# Acoustics_Hydrophone_Process.net
KiCad netlist of a schematic drawn in Altium Designer
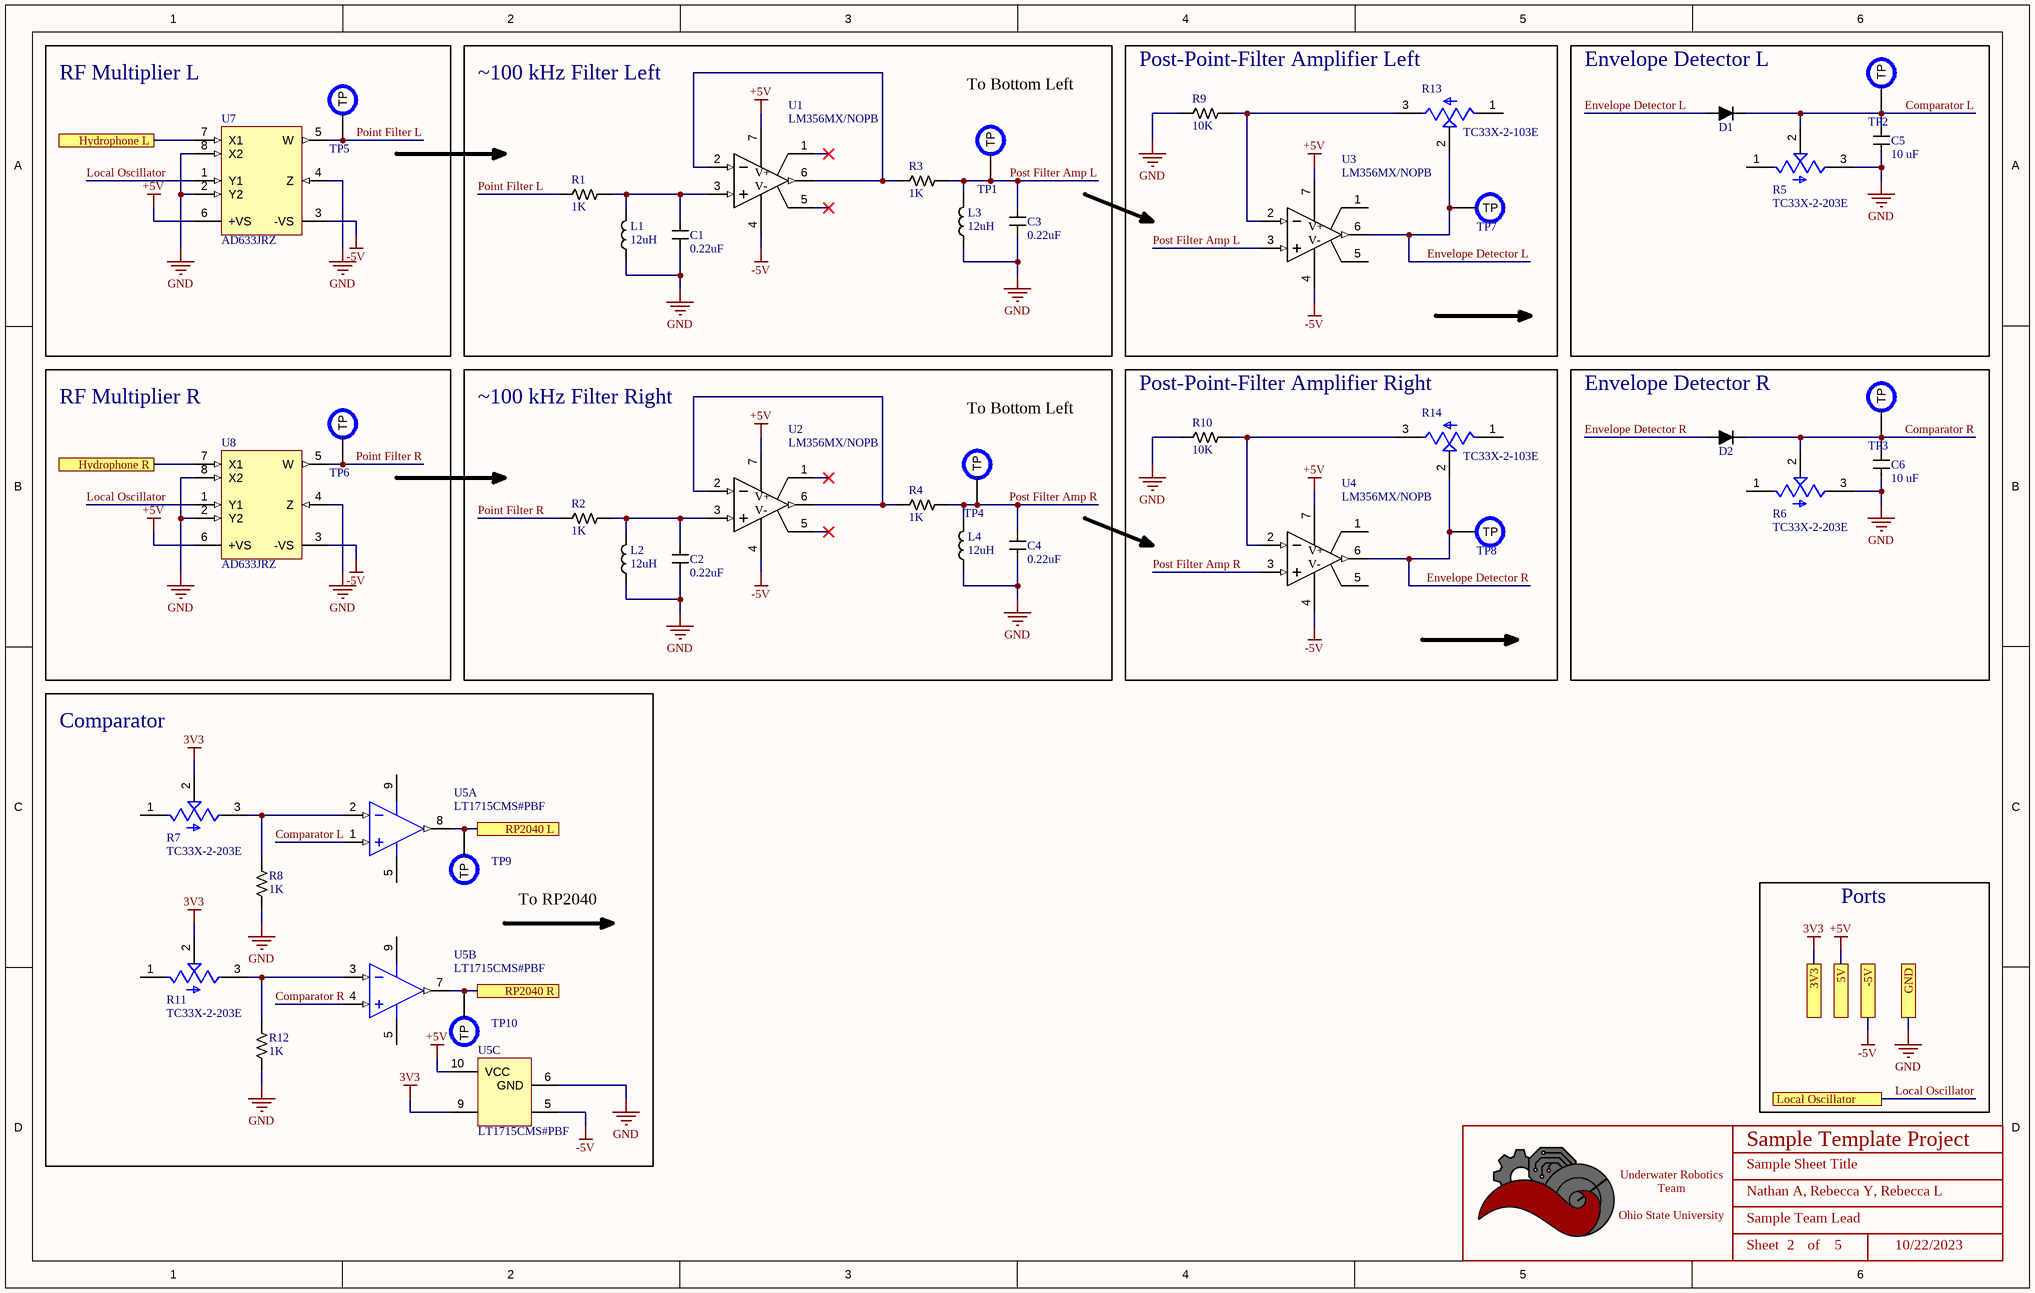
[diagram p0: [Acoustics] Hydrophone Process.SchDoc]

(export (version "E")
  (design (tool "Eeschema 10.0.6"))
  (components
    (comp (ref "C1")
      (value "0.22uF")
      (footprint "CAPACITOR_0603")
      (description "CAP CER 0.22uF 16V X7R 0603")
      (fields
        (field (name "TOLERANCE") "+/- 5%")
        (field (name "VOLTAGE") "16V")
        (field (name "MADE BY") "Nathan Ayer")
      )
      (libsource (lib "Capacitors") (part "CAPACITOR_0.000027uF_0603"))
    )
    (comp (ref "C2")
      (value "0.22uF")
      (footprint "CAPACITOR_0603")
      (description "CAP CER 0.22uF 16V X7R 0603")
      (fields
        (field (name "TOLERANCE") "+/- 5%")
        (field (name "VOLTAGE") "16V")
        (field (name "MADE BY") "Nathan Ayer")
      )
      (libsource (lib "Capacitors") (part "CAPACITOR_0.000027uF_0603"))
    )
    (comp (ref "C3")
      (value "0.22uF")
      (footprint "CAPACITOR_0603")
      (description "CAP CER 0.22uF 16V X7R 0603")
      (fields
        (field (name "TOLERANCE") "+/- 5%")
        (field (name "VOLTAGE") "16V")
        (field (name "MADE BY") "Nathan Ayer")
      )
      (libsource (lib "Capacitors") (part "CAPACITOR_0.000027uF_0603"))
    )
    (comp (ref "C4")
      (value "0.22uF")
      (footprint "CAPACITOR_0603")
      (description "CAP CER 0.22uF 16V X7R 0603")
      (fields
        (field (name "TOLERANCE") "+/- 5%")
        (field (name "VOLTAGE") "16V")
        (field (name "MADE BY") "Nathan Ayer")
      )
      (libsource (lib "Capacitors") (part "CAPACITOR_0.000027uF_0603"))
    )
    (comp (ref "C5")
      (value "10uF Ceramic 6.3V")
      (footprint "CAPACITOR_0603")
      (description "Cap 10uF 6.3V +/-20%\r\nCeramic 0603")
      (fields
        (field (name "TOLERANCE") "+/- 20%")
        (field (name "VOLTAGE") "6.3V")
        (field (name "VALUE (UF)") "10 uF")
        (field (name "MADE BY") "Flip B")
      )
      (libsource (lib "Capacitors") (part "CAPACITOR_10uF_0603"))
    )
    (comp (ref "C6")
      (value "10uF Ceramic 6.3V")
      (footprint "CAPACITOR_0603")
      (description "Cap 10uF 6.3V +/-20%\r\nCeramic 0603")
      (fields
        (field (name "TOLERANCE") "+/- 20%")
        (field (name "VOLTAGE") "6.3V")
        (field (name "VALUE (UF)") "10 uF")
        (field (name "MADE BY") "Flip B")
      )
      (libsource (lib "Capacitors") (part "CAPACITOR_10uF_0603"))
    )
    (comp (ref "D1")
      (value "BAR9002ELE6327XTMA1")
      (footprint "DIODE_0402")
      (description "RF Diode PIN - Single 80V 100 mA 250 mW PG-TSLP-2-19")
      (libsource (lib "Diodes") (part "RF Diode 80V 100mA"))
    )
    (comp (ref "D2")
      (value "BAR9002ELE6327XTMA1")
      (footprint "DIODE_0402")
      (description "RF Diode PIN - Single 80V 100 mA 250 mW PG-TSLP-2-19")
      (libsource (lib "Diodes") (part "RF Diode 80V 100mA"))
    )
    (comp (ref "L1")
      (value "12uH")
      (footprint "INDUCTOR_0603")
      (description "12 µH Shielded Multilayer Inductor 10 mA 1.8Ohm Max 0603 (1608 Metric)")
      (fields
        (field (name "TOLERANCE") "+/- 5%")
        (field (name "Comment") "FIXED IND 12UH 10MA 1.8 OHM SMD")
        (field (name "MADE BY") "Nathan Ayer")
      )
      (libsource (lib "Inductors") (part "INDUCTOR_12uH_0603"))
    )
    (comp (ref "L2")
      (value "12uH")
      (footprint "INDUCTOR_0603")
      (description "12 µH Shielded Multilayer Inductor 10 mA 1.8Ohm Max 0603 (1608 Metric)")
      (fields
        (field (name "TOLERANCE") "+/- 5%")
        (field (name "Comment") "FIXED IND 12UH 10MA 1.8 OHM SMD")
        (field (name "MADE BY") "Nathan Ayer")
      )
      (libsource (lib "Inductors") (part "INDUCTOR_12uH_0603"))
    )
    (comp (ref "L3")
      (value "12uH")
      (footprint "INDUCTOR_0603")
      (description "12 µH Shielded Multilayer Inductor 10 mA 1.8Ohm Max 0603 (1608 Metric)")
      (fields
        (field (name "TOLERANCE") "+/- 5%")
        (field (name "Comment") "FIXED IND 12UH 10MA 1.8 OHM SMD")
        (field (name "MADE BY") "Nathan Ayer")
      )
      (libsource (lib "Inductors") (part "INDUCTOR_12uH_0603"))
    )
    (comp (ref "L4")
      (value "12uH")
      (footprint "INDUCTOR_0603")
      (description "12 µH Shielded Multilayer Inductor 10 mA 1.8Ohm Max 0603 (1608 Metric)")
      (fields
        (field (name "TOLERANCE") "+/- 5%")
        (field (name "Comment") "FIXED IND 12UH 10MA 1.8 OHM SMD")
        (field (name "MADE BY") "Nathan Ayer")
      )
      (libsource (lib "Inductors") (part "INDUCTOR_12uH_0603"))
    )
    (comp (ref "R1")
      (value "1.45k Ohm 0.1% 1/10W")
      (footprint "RESISTOR_0603")
      (description "RES 1.45K OHM 0.1% 1/10W 0603")
      (fields
        (field (name "TOLERANCE") "+/- 0.1%")
        (field (name "VALUE  (OHMS)") "1K")
        (field (name "MADE BY") "Nathan Ayer")
      )
      (libsource (lib "Resistors") (part "RESISTOR_1K_0603"))
    )
    (comp (ref "R2")
      (value "1.45k Ohm 0.1% 1/10W")
      (footprint "RESISTOR_0603")
      (description "RES 1.45K OHM 0.1% 1/10W 0603")
      (fields
        (field (name "TOLERANCE") "+/- 0.1%")
        (field (name "VALUE  (OHMS)") "1K")
        (field (name "MADE BY") "Nathan Ayer")
      )
      (libsource (lib "Resistors") (part "RESISTOR_1K_0603"))
    )
    (comp (ref "R3")
      (value "1.45k Ohm 0.1% 1/10W")
      (footprint "RESISTOR_0603")
      (description "RES 1.45K OHM 0.1% 1/10W 0603")
      (fields
        (field (name "TOLERANCE") "+/- 0.1%")
        (field (name "VALUE  (OHMS)") "1K")
        (field (name "MADE BY") "Nathan Ayer")
      )
      (libsource (lib "Resistors") (part "RESISTOR_1K_0603"))
    )
    (comp (ref "R4")
      (value "1.45k Ohm 0.1% 1/10W")
      (footprint "RESISTOR_0603")
      (description "RES 1.45K OHM 0.1% 1/10W 0603")
      (fields
        (field (name "TOLERANCE") "+/- 0.1%")
        (field (name "VALUE  (OHMS)") "1K")
        (field (name "MADE BY") "Nathan Ayer")
      )
      (libsource (lib "Resistors") (part "RESISTOR_1K_0603"))
    )
    (comp (ref "R5")
      (value "TC33X-2-203E")
      (footprint "TRIM_TC33X-2-203E")
      (description "20 kOhms 0.1W, 1/10W J Lead Surface Mount Trimmer Potentiometer Cermet 1 Turn Top Adjustment")
      (fields (field (name "MF") "Bourns") (field (name "DIGI-KEY_PART_NUMBER") "TC33X-2-203ECT-ND"))
      (libsource (lib "Resistors") (part "TC33X-2-203E"))
    )
    (comp (ref "R6")
      (value "TC33X-2-203E")
      (footprint "TRIM_TC33X-2-203E")
      (description "20 kOhms 0.1W, 1/10W J Lead Surface Mount Trimmer Potentiometer Cermet 1 Turn Top Adjustment")
      (fields (field (name "MF") "Bourns") (field (name "DIGI-KEY_PART_NUMBER") "TC33X-2-203ECT-ND"))
      (libsource (lib "Resistors") (part "TC33X-2-203E"))
    )
    (comp (ref "R7")
      (value "TC33X-2-203E")
      (footprint "TRIM_TC33X-2-203E")
      (description "20 kOhms 0.1W, 1/10W J Lead Surface Mount Trimmer Potentiometer Cermet 1 Turn Top Adjustment")
      (fields (field (name "MF") "Bourns") (field (name "DIGI-KEY_PART_NUMBER") "TC33X-2-203ECT-ND"))
      (libsource (lib "Resistors") (part "TC33X-2-203E"))
    )
    (comp (ref "R8")
      (value "1k Ohm 1% 1/16W")
      (footprint "RESISTOR_0402")
      (description "RES 1k OHM 1% 1/16W 0402")
      (fields
        (field (name "TOLERANCE") "+/- 1%")
        (field (name "VALUE  (OHMS)") "1K")
        (field (name "MADE BY") "Robert Pafford")
      )
      (libsource (lib "Resistors") (part "RESISTOR_1K_0402"))
    )
    (comp (ref "R9")
      (value "10k Ohm 0.5% 1/10W")
      (footprint "RESISTOR_0603")
      (description "RES 10k OHM 0.5% 1/10W 0603")
      (fields
        (field (name "TOLERANCE") "+/- 0.5%")
        (field (name "VALUE  (OHMS)") "10K")
        (field (name "MADE BY") "Robert Pafford")
      )
      (libsource (lib "Resistors") (part "RESISTOR_10K_0.5%_0603"))
    )
    (comp (ref "R10")
      (value "10k Ohm 0.5% 1/10W")
      (footprint "RESISTOR_0603")
      (description "RES 10k OHM 0.5% 1/10W 0603")
      (fields
        (field (name "TOLERANCE") "+/- 0.5%")
        (field (name "VALUE  (OHMS)") "10K")
        (field (name "MADE BY") "Robert Pafford")
      )
      (libsource (lib "Resistors") (part "RESISTOR_10K_0.5%_0603"))
    )
    (comp (ref "R11")
      (value "TC33X-2-203E")
      (footprint "TRIM_TC33X-2-203E")
      (description "20 kOhms 0.1W, 1/10W J Lead Surface Mount Trimmer Potentiometer Cermet 1 Turn Top Adjustment")
      (fields (field (name "MF") "Bourns") (field (name "DIGI-KEY_PART_NUMBER") "TC33X-2-203ECT-ND"))
      (libsource (lib "Resistors") (part "TC33X-2-203E"))
    )
    (comp (ref "R12")
      (value "1k Ohm 1% 1/16W")
      (footprint "RESISTOR_0402")
      (description "RES 1k OHM 1% 1/16W 0402")
      (fields
        (field (name "TOLERANCE") "+/- 1%")
        (field (name "VALUE  (OHMS)") "1K")
        (field (name "MADE BY") "Robert Pafford")
      )
      (libsource (lib "Resistors") (part "RESISTOR_1K_0402"))
    )
    (comp (ref "R13")
      (value "TC33X-2-103E")
      (footprint "TRIM_TC33X-2-203E")
      (description "20 kOhms 0.1W, 1/10W J Lead Surface Mount Trimmer Potentiometer Cermet 1 Turn Top Adjustment")
      (fields (field (name "MF") "Bourns") (field (name "DIGI-KEY_PART_NUMBER") "TC33X-2-203ECT-ND"))
      (libsource (lib "Resistors") (part "TC33X-2-203E"))
    )
    (comp (ref "R14")
      (value "TC33X-2-103E")
      (footprint "TRIM_TC33X-2-203E")
      (description "20 kOhms 0.1W, 1/10W J Lead Surface Mount Trimmer Potentiometer Cermet 1 Turn Top Adjustment")
      (fields (field (name "MF") "Bourns") (field (name "DIGI-KEY_PART_NUMBER") "TC33X-2-203ECT-ND"))
      (libsource (lib "Resistors") (part "TC33X-2-203E"))
    )
    (comp (ref "TP1")
      (value "PCB Test Point")
      (footprint "TESTPOINT_1.2MM")
      (fields (field (name "MADE BY") "Robert Pafford"))
      (libsource (lib "Connectors") (part "TESTPOINT"))
    )
    (comp (ref "TP2")
      (value "PCB Test Point")
      (footprint "TESTPOINT_1.2MM")
      (fields (field (name "MADE BY") "Robert Pafford"))
      (libsource (lib "Connectors") (part "TESTPOINT"))
    )
    (comp (ref "TP3")
      (value "PCB Test Point")
      (footprint "TESTPOINT_1.2MM")
      (fields (field (name "MADE BY") "Robert Pafford"))
      (libsource (lib "Connectors") (part "TESTPOINT"))
    )
    (comp (ref "TP4")
      (value "PCB Test Point")
      (footprint "TESTPOINT_1.2MM")
      (fields (field (name "MADE BY") "Robert Pafford"))
      (libsource (lib "Connectors") (part "TESTPOINT"))
    )
    (comp (ref "TP5")
      (value "PCB Test Point")
      (footprint "TESTPOINT_1.2MM")
      (fields (field (name "MADE BY") "Robert Pafford"))
      (libsource (lib "Connectors") (part "TESTPOINT"))
    )
    (comp (ref "TP6")
      (value "PCB Test Point")
      (footprint "TESTPOINT_1.2MM")
      (fields (field (name "MADE BY") "Robert Pafford"))
      (libsource (lib "Connectors") (part "TESTPOINT"))
    )
    (comp (ref "TP7")
      (value "PCB Test Point")
      (footprint "TESTPOINT_1.2MM")
      (fields (field (name "MADE BY") "Robert Pafford"))
      (libsource (lib "Connectors") (part "TESTPOINT"))
    )
    (comp (ref "TP8")
      (value "PCB Test Point")
      (footprint "TESTPOINT_1.2MM")
      (fields (field (name "MADE BY") "Robert Pafford"))
      (libsource (lib "Connectors") (part "TESTPOINT"))
    )
    (comp (ref "TP9")
      (value "PCB Test Point")
      (footprint "TESTPOINT_1.2MM")
      (fields (field (name "MADE BY") "Robert Pafford"))
      (libsource (lib "Connectors") (part "TESTPOINT"))
    )
    (comp (ref "TP10")
      (value "PCB Test Point")
      (footprint "TESTPOINT_1.2MM")
      (fields (field (name "MADE BY") "Robert Pafford"))
      (libsource (lib "Connectors") (part "TESTPOINT"))
    )
    (comp (ref "U1")
      (value "LM356MX/NOPB")
      (footprint "SOIC-8")
      (description "IC OPAMP JFET 1 CIRCUIT 8SOIC")
      (fields
        (field (name "PARTNUMBER") "LM8261M5X/NOPB")
        (field (name "MANUFACTURER") "Texas Instruments")
        (field (name "CREATED BY") "Dylan T")
      )
      (libsource (lib "Integrated Circuits") (part "LM356MX/NOPB"))
    )
    (comp (ref "U2")
      (value "LM356MX/NOPB")
      (footprint "SOIC-8")
      (description "IC OPAMP JFET 1 CIRCUIT 8SOIC")
      (fields
        (field (name "PARTNUMBER") "LM8261M5X/NOPB")
        (field (name "MANUFACTURER") "Texas Instruments")
        (field (name "CREATED BY") "Dylan T")
      )
      (libsource (lib "Integrated Circuits") (part "LM356MX/NOPB"))
    )
    (comp (ref "U3")
      (value "LM356MX/NOPB")
      (footprint "SOIC-8")
      (description "IC OPAMP JFET 1 CIRCUIT 8SOIC")
      (fields
        (field (name "PARTNUMBER") "LM8261M5X/NOPB")
        (field (name "MANUFACTURER") "Texas Instruments")
        (field (name "CREATED BY") "Dylan T")
      )
      (libsource (lib "Integrated Circuits") (part "LM356MX/NOPB"))
    )
    (comp (ref "U4")
      (value "LM356MX/NOPB")
      (footprint "SOIC-8")
      (description "IC OPAMP JFET 1 CIRCUIT 8SOIC")
      (fields
        (field (name "PARTNUMBER") "LM8261M5X/NOPB")
        (field (name "MANUFACTURER") "Texas Instruments")
        (field (name "CREATED BY") "Dylan T")
      )
      (libsource (lib "Integrated Circuits") (part "LM356MX/NOPB"))
    )
    (comp (ref "U5")
      (value "LT1715CMS#PBF")
      (footprint "LT-MS10_N")
      (fields (field (name "GENERIC PART NUMBER") "LT1715") (field (name "MANUFACTURER") "Linear Technology"))
      (libsource (lib "") (part "LT-LT1715-MSOP10_1"))
    )
    (comp (ref "U7")
      (value "AD633JRZ")
      (footprint "ADI-R-8_M")
      (description "Low Cost Analog Multiplier, 20 V/us, 6 mA, 0 to 70 degC, 8-Pin SOIC (R), RoHS, Tube")
      (fields (field (name "PARTNUMBER") "AD633"))
      (libsource (lib "Altium Content Vault") (part "ADI-AD633-R-8"))
    )
    (comp (ref "U8")
      (value "AD633JRZ")
      (footprint "ADI-R-8_M")
      (description "Low Cost Analog Multiplier, 20 V/us, 6 mA, 0 to 70 degC, 8-Pin SOIC (R), RoHS, Tube")
      (fields (field (name "PARTNUMBER") "AD633"))
      (libsource (lib "Altium Content Vault") (part "ADI-AD633-R-8"))
    )
  )
  (nets
    (net (code "1") (name "+5V") (class "Default")
      (node (ref "U1") (pin "7") (pinfunction "V+_7") (pintype "power_in"))
      (node (ref "U2") (pin "7") (pinfunction "V+_7") (pintype "power_in"))
      (node (ref "U3") (pin "7") (pinfunction "V+_7") (pintype "power_in"))
      (node (ref "U4") (pin "7") (pinfunction "V+_7") (pintype "power_in"))
      (node (ref "U5") (pin "10") (pinfunction "VCC_10") (pintype "power_in"))
      (node (ref "U7") (pin "6") (pinfunction "+VS_6") (pintype "power_in"))
      (node (ref "U8") (pin "6") (pinfunction "+VS_6") (pintype "power_in"))
    )
    (net (code "2") (name "-5V") (class "Default")
      (node (ref "U1") (pin "4") (pinfunction "V-_4") (pintype "power_in"))
      (node (ref "U2") (pin "4") (pinfunction "V-_4") (pintype "power_in"))
      (node (ref "U3") (pin "4") (pinfunction "V-_4") (pintype "power_in"))
      (node (ref "U4") (pin "4") (pinfunction "V-_4") (pintype "power_in"))
      (node (ref "U5") (pin "5") (pinfunction "VEE_5") (pintype "power_in"))
      (node (ref "U7") (pin "3") (pinfunction "-VS_3") (pintype "power_in"))
      (node (ref "U8") (pin "3") (pinfunction "-VS_3") (pintype "power_in"))
    )
    (net (code "4") (name "/Comparator L") (class "Default")
      (node (ref "C5") (pin "1") (pinfunction "1_1") (pintype "passive"))
      (node (ref "D1") (pin "2") (pinfunction "2_2") (pintype "passive"))
      (node (ref "R5") (pin "2") (pinfunction "W_2") (pintype "passive"))
      (node (ref "TP2") (pin "TP") (pinfunction "TP_TP") (pintype "passive"))
      (node (ref "U5") (pin "1") (pinfunction "+IN_A_1") (pintype "input"))
    )
    (net (code "5") (name "/Comparator R") (class "Default")
      (node (ref "C6") (pin "1") (pinfunction "1_1") (pintype "passive"))
      (node (ref "D2") (pin "2") (pinfunction "2_2") (pintype "passive"))
      (node (ref "R6") (pin "2") (pinfunction "W_2") (pintype "passive"))
      (node (ref "TP3") (pin "TP") (pinfunction "TP_TP") (pintype "passive"))
      (node (ref "U5") (pin "4") (pinfunction "+IN_B_4") (pintype "input"))
    )
    (net (code "6") (name "/Envelope Detector L") (class "Default")
      (node (ref "D1") (pin "1") (pinfunction "1_1") (pintype "passive"))
      (node (ref "R13") (pin "2") (pinfunction "W_2") (pintype "passive"))
      (node (ref "TP7") (pin "TP") (pinfunction "TP_TP") (pintype "passive"))
      (node (ref "U3") (pin "6") (pinfunction "OUT_6") (pintype "output"))
    )
    (net (code "7") (name "/Envelope Detector R") (class "Default")
      (node (ref "D2") (pin "1") (pinfunction "1_1") (pintype "passive"))
      (node (ref "R14") (pin "2") (pinfunction "W_2") (pintype "passive"))
      (node (ref "TP8") (pin "TP") (pinfunction "TP_TP") (pintype "passive"))
      (node (ref "U4") (pin "6") (pinfunction "OUT_6") (pintype "output"))
    )
    (net (code "8") (name "/Hydrophone L") (class "Default")
      (node (ref "U7") (pin "7") (pinfunction "X1_7") (pintype "input"))
    )
    (net (code "9") (name "/Hydrophone R") (class "Default")
      (node (ref "U8") (pin "7") (pinfunction "X1_7") (pintype "input"))
    )
    (net (code "10") (name "/Local Oscillator") (class "Default")
      (node (ref "U7") (pin "1") (pinfunction "Y1_1") (pintype "input"))
      (node (ref "U8") (pin "1") (pinfunction "Y1_1") (pintype "input"))
    )
    (net (code "11") (name "/Point Filter L") (class "Default")
      (node (ref "R1") (pin "2") (pinfunction "2_2") (pintype "passive"))
      (node (ref "TP5") (pin "TP") (pinfunction "TP_TP") (pintype "passive"))
      (node (ref "U7") (pin "5") (pinfunction "W_5") (pintype "output"))
    )
    (net (code "12") (name "/Point Filter R") (class "Default")
      (node (ref "R2") (pin "2") (pinfunction "2_2") (pintype "passive"))
      (node (ref "TP6") (pin "TP") (pinfunction "TP_TP") (pintype "passive"))
      (node (ref "U8") (pin "5") (pinfunction "W_5") (pintype "output"))
    )
    (net (code "13") (name "/Post Filter Amp L") (class "Default")
      (node (ref "C3") (pin "1") (pinfunction "1_1") (pintype "passive"))
      (node (ref "L3") (pin "1") (pinfunction "1_1") (pintype "passive"))
      (node (ref "R3") (pin "1") (pinfunction "1_1") (pintype "passive"))
      (node (ref "TP1") (pin "TP") (pinfunction "TP_TP") (pintype "passive"))
      (node (ref "U3") (pin "3") (pinfunction "IN+_3") (pintype "input"))
    )
    (net (code "14") (name "/Post Filter Amp R") (class "Default")
      (node (ref "C4") (pin "1") (pinfunction "1_1") (pintype "passive"))
      (node (ref "L4") (pin "1") (pinfunction "1_1") (pintype "passive"))
      (node (ref "R4") (pin "1") (pinfunction "1_1") (pintype "passive"))
      (node (ref "TP4") (pin "TP") (pinfunction "TP_TP") (pintype "passive"))
      (node (ref "U4") (pin "3") (pinfunction "IN+_3") (pintype "input"))
    )
    (net (code "15") (name "/RP2040 L") (class "Default")
      (node (ref "TP9") (pin "TP") (pinfunction "TP_TP") (pintype "passive"))
      (node (ref "U5") (pin "8") (pinfunction "OUT_A_8") (pintype "output"))
    )
    (net (code "16") (name "/RP2040 R") (class "Default")
      (node (ref "TP10") (pin "TP") (pinfunction "TP_TP") (pintype "passive"))
      (node (ref "U5") (pin "7") (pinfunction "OUT_B_7") (pintype "output"))
    )
    (net (code "17") (name "3V3") (class "Default")
      (node (ref "R11") (pin "2") (pinfunction "W_2") (pintype "passive"))
      (node (ref "R7") (pin "2") (pinfunction "W_2") (pintype "passive"))
      (node (ref "U5") (pin "9") (pinfunction "+VS_9") (pintype "power_in"))
    )
    (net (code "18") (name "GND") (class "Default")
      (node (ref "C1") (pin "2") (pinfunction "2_2") (pintype "passive"))
      (node (ref "C2") (pin "2") (pinfunction "2_2") (pintype "passive"))
      (node (ref "C3") (pin "2") (pinfunction "2_2") (pintype "passive"))
      (node (ref "C4") (pin "2") (pinfunction "2_2") (pintype "passive"))
      (node (ref "C5") (pin "2") (pinfunction "2_2") (pintype "passive"))
      (node (ref "C6") (pin "2") (pinfunction "2_2") (pintype "passive"))
      (node (ref "L1") (pin "2") (pinfunction "2_2") (pintype "passive"))
      (node (ref "L2") (pin "2") (pinfunction "2_2") (pintype "passive"))
      (node (ref "L3") (pin "2") (pinfunction "2_2") (pintype "passive"))
      (node (ref "L4") (pin "2") (pinfunction "2_2") (pintype "passive"))
      (node (ref "R10") (pin "2") (pinfunction "2_2") (pintype "passive"))
      (node (ref "R12") (pin "2") (pinfunction "2_2") (pintype "passive"))
      (node (ref "R5") (pin "3") (pinfunction "CW_3") (pintype "passive"))
      (node (ref "R6") (pin "3") (pinfunction "CW_3") (pintype "passive"))
      (node (ref "R8") (pin "2") (pinfunction "2_2") (pintype "passive"))
      (node (ref "R9") (pin "2") (pinfunction "2_2") (pintype "passive"))
      (node (ref "U5") (pin "6") (pinfunction "GND_6") (pintype "power_in"))
      (node (ref "U7") (pin "2") (pinfunction "Y2_2") (pintype "input"))
      (node (ref "U7") (pin "4") (pinfunction "Z_4") (pintype "input"))
      (node (ref "U7") (pin "8") (pinfunction "X2_8") (pintype "input"))
      (node (ref "U8") (pin "2") (pinfunction "Y2_2") (pintype "input"))
      (node (ref "U8") (pin "4") (pinfunction "Z_4") (pintype "input"))
      (node (ref "U8") (pin "8") (pinfunction "X2_8") (pintype "input"))
    )
    (net (code "19") (name "Net-(R7-CW)") (class "Default")
      (node (ref "R7") (pin "3") (pinfunction "CW_3") (pintype "passive"))
      (node (ref "R8") (pin "1") (pinfunction "1_1") (pintype "passive"))
      (node (ref "U5") (pin "2") (pinfunction "-IN_A_2") (pintype "input"))
    )
    (net (code "20") (name "Net-(R11-CW)") (class "Default")
      (node (ref "R11") (pin "3") (pinfunction "CW_3") (pintype "passive"))
      (node (ref "R12") (pin "1") (pinfunction "1_1") (pintype "passive"))
      (node (ref "U5") (pin "3") (pinfunction "-IN_B_3") (pintype "input"))
    )
    (net (code "21") (name "Net-(R13-CW)") (class "Default")
      (node (ref "R13") (pin "3") (pinfunction "CW_3") (pintype "passive"))
      (node (ref "R9") (pin "1") (pinfunction "1_1") (pintype "passive"))
      (node (ref "U3") (pin "2") (pinfunction "IN-_2") (pintype "input"))
    )
    (net (code "22") (name "Net-(R14-CW)") (class "Default")
      (node (ref "R10") (pin "1") (pinfunction "1_1") (pintype "passive"))
      (node (ref "R14") (pin "3") (pinfunction "CW_3") (pintype "passive"))
      (node (ref "U4") (pin "2") (pinfunction "IN-_2") (pintype "input"))
    )
    (net (code "23") (name "Net-(U1-IN+)") (class "Default")
      (node (ref "C1") (pin "1") (pinfunction "1_1") (pintype "passive"))
      (node (ref "L1") (pin "1") (pinfunction "1_1") (pintype "passive"))
      (node (ref "R1") (pin "1") (pinfunction "1_1") (pintype "passive"))
      (node (ref "U1") (pin "3") (pinfunction "IN+_3") (pintype "input"))
    )
    (net (code "24") (name "Net-(U1-IN-)") (class "Default")
      (node (ref "R3") (pin "2") (pinfunction "2_2") (pintype "passive"))
      (node (ref "U1") (pin "2") (pinfunction "IN-_2") (pintype "input"))
      (node (ref "U1") (pin "6") (pinfunction "OUT_6") (pintype "output"))
    )
    (net (code "25") (name "Net-(U2-IN+)") (class "Default")
      (node (ref "C2") (pin "1") (pinfunction "1_1") (pintype "passive"))
      (node (ref "L2") (pin "1") (pinfunction "1_1") (pintype "passive"))
      (node (ref "R2") (pin "1") (pinfunction "1_1") (pintype "passive"))
      (node (ref "U2") (pin "3") (pinfunction "IN+_3") (pintype "input"))
    )
    (net (code "26") (name "Net-(U2-IN-)") (class "Default")
      (node (ref "R4") (pin "2") (pinfunction "2_2") (pintype "passive"))
      (node (ref "U2") (pin "2") (pinfunction "IN-_2") (pintype "input"))
      (node (ref "U2") (pin "6") (pinfunction "OUT_6") (pintype "output"))
    )
    (net (code "27") (name "unconnected-(R5-CCW-Pad1)") (class "Default")
      (node (ref "R5") (pin "1") (pinfunction "CCW_1") (pintype "passive"))
    )
    (net (code "28") (name "unconnected-(R6-CCW-Pad1)") (class "Default")
      (node (ref "R6") (pin "1") (pinfunction "CCW_1") (pintype "passive"))
    )
    (net (code "29") (name "unconnected-(R7-CCW-Pad1)") (class "Default")
      (node (ref "R7") (pin "1") (pinfunction "CCW_1") (pintype "passive"))
    )
    (net (code "30") (name "unconnected-(R11-CCW-Pad1)") (class "Default")
      (node (ref "R11") (pin "1") (pinfunction "CCW_1") (pintype "passive"))
    )
    (net (code "31") (name "unconnected-(R13-CCW-Pad1)") (class "Default")
      (node (ref "R13") (pin "1") (pinfunction "CCW_1") (pintype "passive"))
    )
    (net (code "32") (name "unconnected-(R14-CCW-Pad1)") (class "Default")
      (node (ref "R14") (pin "1") (pinfunction "CCW_1") (pintype "passive"))
    )
    (net (code "33") (name "unconnected-(U1-Balance-Pad1)") (class "Default")
      (node (ref "U1") (pin "1") (pinfunction "Balance_1") (pintype "passive+no_connect"))
    )
    (net (code "34") (name "unconnected-(U1-Balance-Pad5)") (class "Default")
      (node (ref "U1") (pin "5") (pinfunction "Balance_5") (pintype "passive+no_connect"))
    )
    (net (code "35") (name "unconnected-(U2-Balance-Pad1)") (class "Default")
      (node (ref "U2") (pin "1") (pinfunction "Balance_1") (pintype "passive+no_connect"))
    )
    (net (code "36") (name "unconnected-(U2-Balance-Pad5)") (class "Default")
      (node (ref "U2") (pin "5") (pinfunction "Balance_5") (pintype "passive+no_connect"))
    )
    (net (code "37") (name "unconnected-(U3-Balance-Pad1)") (class "Default")
      (node (ref "U3") (pin "1") (pinfunction "Balance_1") (pintype "passive"))
    )
    (net (code "38") (name "unconnected-(U3-Balance-Pad5)") (class "Default")
      (node (ref "U3") (pin "5") (pinfunction "Balance_5") (pintype "passive"))
    )
    (net (code "39") (name "unconnected-(U4-Balance-Pad1)") (class "Default")
      (node (ref "U4") (pin "1") (pinfunction "Balance_1") (pintype "passive"))
    )
    (net (code "40") (name "unconnected-(U4-Balance-Pad5)") (class "Default")
      (node (ref "U4") (pin "5") (pinfunction "Balance_5") (pintype "passive"))
    )
    (net (code "41") (name "unconnected-(U5A-+VS-Pad9)") (class "Default")
      (node (ref "U5") (pin "9") (pinfunction "+VS_9") (pintype "power_in"))
    )
    (net (code "42") (name "unconnected-(U5A-VEE-Pad5)") (class "Default")
      (node (ref "U5") (pin "5") (pinfunction "VEE_5") (pintype "power_in"))
    )
    (net (code "43") (name "unconnected-(U5B-+VS-Pad9)") (class "Default")
      (node (ref "U5") (pin "9") (pinfunction "+VS_9") (pintype "power_in"))
    )
    (net (code "44") (name "unconnected-(U5B-VEE-Pad5)") (class "Default")
      (node (ref "U5") (pin "5") (pinfunction "VEE_5") (pintype "power_in"))
    )
  )
)
